# rfm69_breakout.net
KiCad netlist of a schematic drawn in EAGLE
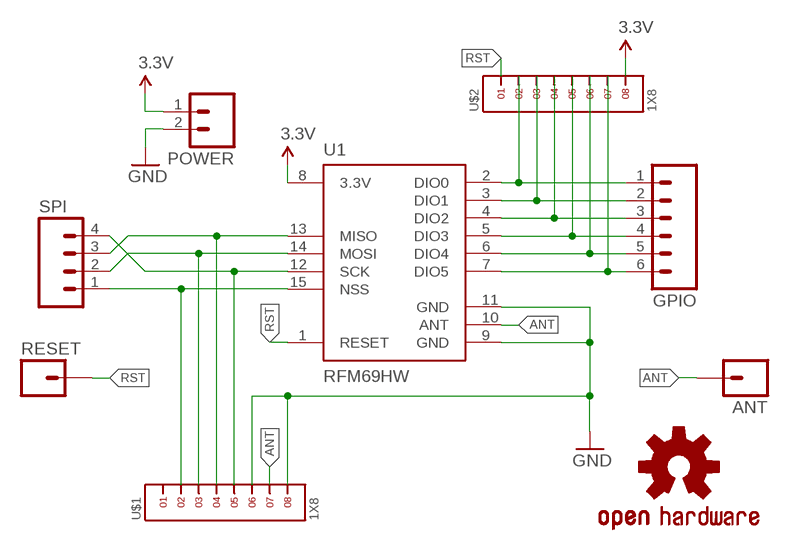
[diagram p0: schematic, sheet 1]

(export (version "E")
  (design (tool "Eeschema 10.0.6"))
  (components
    (comp (ref "ANT")
      (value "M01PTH")
      (footprint "eagle-import:1X01")
      (libsource (lib "eagle-import") (part "M01PTH"))
    )
    (comp (ref "GPIO")
      (value "M06SILK_FEMALE_PTH")
      (footprint "eagle-import:1X06")
      (libsource (lib "eagle-import") (part "M06SILK_FEMALE_PTH"))
    )
    (comp (ref "LOGO1")
      (value "OSHW-LOGOL")
      (footprint "eagle-import:OSHW-LOGO-L")
      (libsource (lib "eagle-import") (part "OSHW-LOGOL"))
    )
    (comp (ref "POWER")
      (value "M02PTH")
      (footprint "eagle-import:1X02")
      (libsource (lib "eagle-import") (part "M02PTH"))
    )
    (comp (ref "RESET")
      (value "M01PTH")
      (footprint "eagle-import:1X01")
      (libsource (lib "eagle-import") (part "M01PTH"))
    )
    (comp (ref "SPI")
      (value "M04PTH")
      (footprint "eagle-import:1X04")
      (libsource (lib "eagle-import") (part "M04PTH"))
    )
    (comp (ref "U$1")
      (value "1X8")
      (footprint "eagle-import:1X8")
      (libsource (lib "eagle-import") (part "1X8"))
    )
    (comp (ref "U$2")
      (value "1X8")
      (footprint "eagle-import:1X8")
      (libsource (lib "eagle-import") (part "1X8"))
    )
    (comp (ref "U1")
      (value "RFM69HW")
      (footprint "eagle-import:RFM69W-XXXS2")
      (libsource (lib "eagle-import") (part "RFM69HW"))
    )
  )
  (nets
    (net (code "1") (name "3.3V") (class "Default")
      (node (ref "POWER") (pin "1") (pinfunction "1_1") (pintype "passive"))
      (node (ref "U$2") (pin "8") (pinfunction "8_8") (pintype "bidirectional"))
      (node (ref "U1") (pin "8") (pinfunction "3.3V_8") (pintype "power_in"))
    )
    (net (code "2") (name "ANT") (class "Default")
      (node (ref "ANT") (pin "1") (pinfunction "1_1") (pintype "passive"))
      (node (ref "U$1") (pin "7") (pinfunction "7_7") (pintype "bidirectional"))
      (node (ref "U1") (pin "10") (pinfunction "ANT_10") (pintype "passive"))
    )
    (net (code "3") (name "GND") (class "Default")
      (node (ref "POWER") (pin "2") (pinfunction "2_2") (pintype "passive"))
      (node (ref "U$1") (pin "6") (pinfunction "6_6") (pintype "bidirectional"))
      (node (ref "U$1") (pin "8") (pinfunction "8_8") (pintype "bidirectional"))
      (node (ref "U1") (pin "11") (pinfunction "GND_11") (pintype "power_in"))
      (node (ref "U1") (pin "9") (pinfunction "GND_9") (pintype "power_in"))
    )
    (net (code "4") (name "Net-(U1-DIO0)") (class "Default")
      (node (ref "GPIO") (pin "1") (pinfunction "1_1") (pintype "passive"))
      (node (ref "U$2") (pin "2") (pinfunction "2_2") (pintype "bidirectional"))
      (node (ref "U1") (pin "2") (pinfunction "DIO0_2") (pintype "bidirectional"))
    )
    (net (code "5") (name "Net-(U1-DIO1)") (class "Default")
      (node (ref "GPIO") (pin "2") (pinfunction "2_2") (pintype "passive"))
      (node (ref "U$2") (pin "3") (pinfunction "3_3") (pintype "bidirectional"))
      (node (ref "U1") (pin "3") (pinfunction "DIO1_3") (pintype "bidirectional"))
    )
    (net (code "6") (name "Net-(U1-DIO2)") (class "Default")
      (node (ref "GPIO") (pin "3") (pinfunction "3_3") (pintype "passive"))
      (node (ref "U$2") (pin "4") (pinfunction "4_4") (pintype "bidirectional"))
      (node (ref "U1") (pin "4") (pinfunction "DIO2_4") (pintype "bidirectional"))
    )
    (net (code "7") (name "Net-(U1-DIO3)") (class "Default")
      (node (ref "GPIO") (pin "4") (pinfunction "4_4") (pintype "passive"))
      (node (ref "U$2") (pin "5") (pinfunction "5_5") (pintype "bidirectional"))
      (node (ref "U1") (pin "5") (pinfunction "DIO3_5") (pintype "bidirectional"))
    )
    (net (code "8") (name "Net-(U1-DIO4)") (class "Default")
      (node (ref "GPIO") (pin "5") (pinfunction "5_5") (pintype "passive"))
      (node (ref "U$2") (pin "6") (pinfunction "6_6") (pintype "bidirectional"))
      (node (ref "U1") (pin "6") (pinfunction "DIO4_6") (pintype "bidirectional"))
    )
    (net (code "9") (name "Net-(U1-DIO5)") (class "Default")
      (node (ref "GPIO") (pin "6") (pinfunction "6_6") (pintype "passive"))
      (node (ref "U$2") (pin "7") (pinfunction "7_7") (pintype "bidirectional"))
      (node (ref "U1") (pin "7") (pinfunction "DIO5_7") (pintype "bidirectional"))
    )
    (net (code "10") (name "Net-(U1-MISO)") (class "Default")
      (node (ref "SPI") (pin "3") (pinfunction "3_3") (pintype "passive"))
      (node (ref "U$1") (pin "4") (pinfunction "4_4") (pintype "bidirectional"))
      (node (ref "U1") (pin "13") (pinfunction "MISO_13") (pintype "bidirectional"))
    )
    (net (code "11") (name "Net-(U1-MOSI)") (class "Default")
      (node (ref "SPI") (pin "2") (pinfunction "2_2") (pintype "passive"))
      (node (ref "U$1") (pin "3") (pinfunction "3_3") (pintype "bidirectional"))
      (node (ref "U1") (pin "14") (pinfunction "MOSI_14") (pintype "input"))
    )
    (net (code "12") (name "Net-(U1-NSS)") (class "Default")
      (node (ref "SPI") (pin "1") (pinfunction "1_1") (pintype "passive"))
      (node (ref "U$1") (pin "2") (pinfunction "2_2") (pintype "bidirectional"))
      (node (ref "U1") (pin "15") (pinfunction "NSS_15") (pintype "input"))
    )
    (net (code "13") (name "Net-(U1-SCK)") (class "Default")
      (node (ref "SPI") (pin "4") (pinfunction "4_4") (pintype "passive"))
      (node (ref "U$1") (pin "5") (pinfunction "5_5") (pintype "bidirectional"))
      (node (ref "U1") (pin "12") (pinfunction "SCK_12") (pintype "input"))
    )
    (net (code "14") (name "RST") (class "Default")
      (node (ref "RESET") (pin "1") (pinfunction "1_1") (pintype "passive"))
      (node (ref "U$2") (pin "1") (pinfunction "1_1") (pintype "bidirectional"))
      (node (ref "U1") (pin "1") (pinfunction "RESET_1") (pintype "input"))
    )
    (net (code "15") (name "unconnected-(U$1-Pad1)") (class "Default")
      (node (ref "U$1") (pin "1") (pinfunction "1_1") (pintype "bidirectional"))
    )
  )
)
